# shape_setting_arduino_board.net
KiCad netlist of a schematic drawn in EAGLE
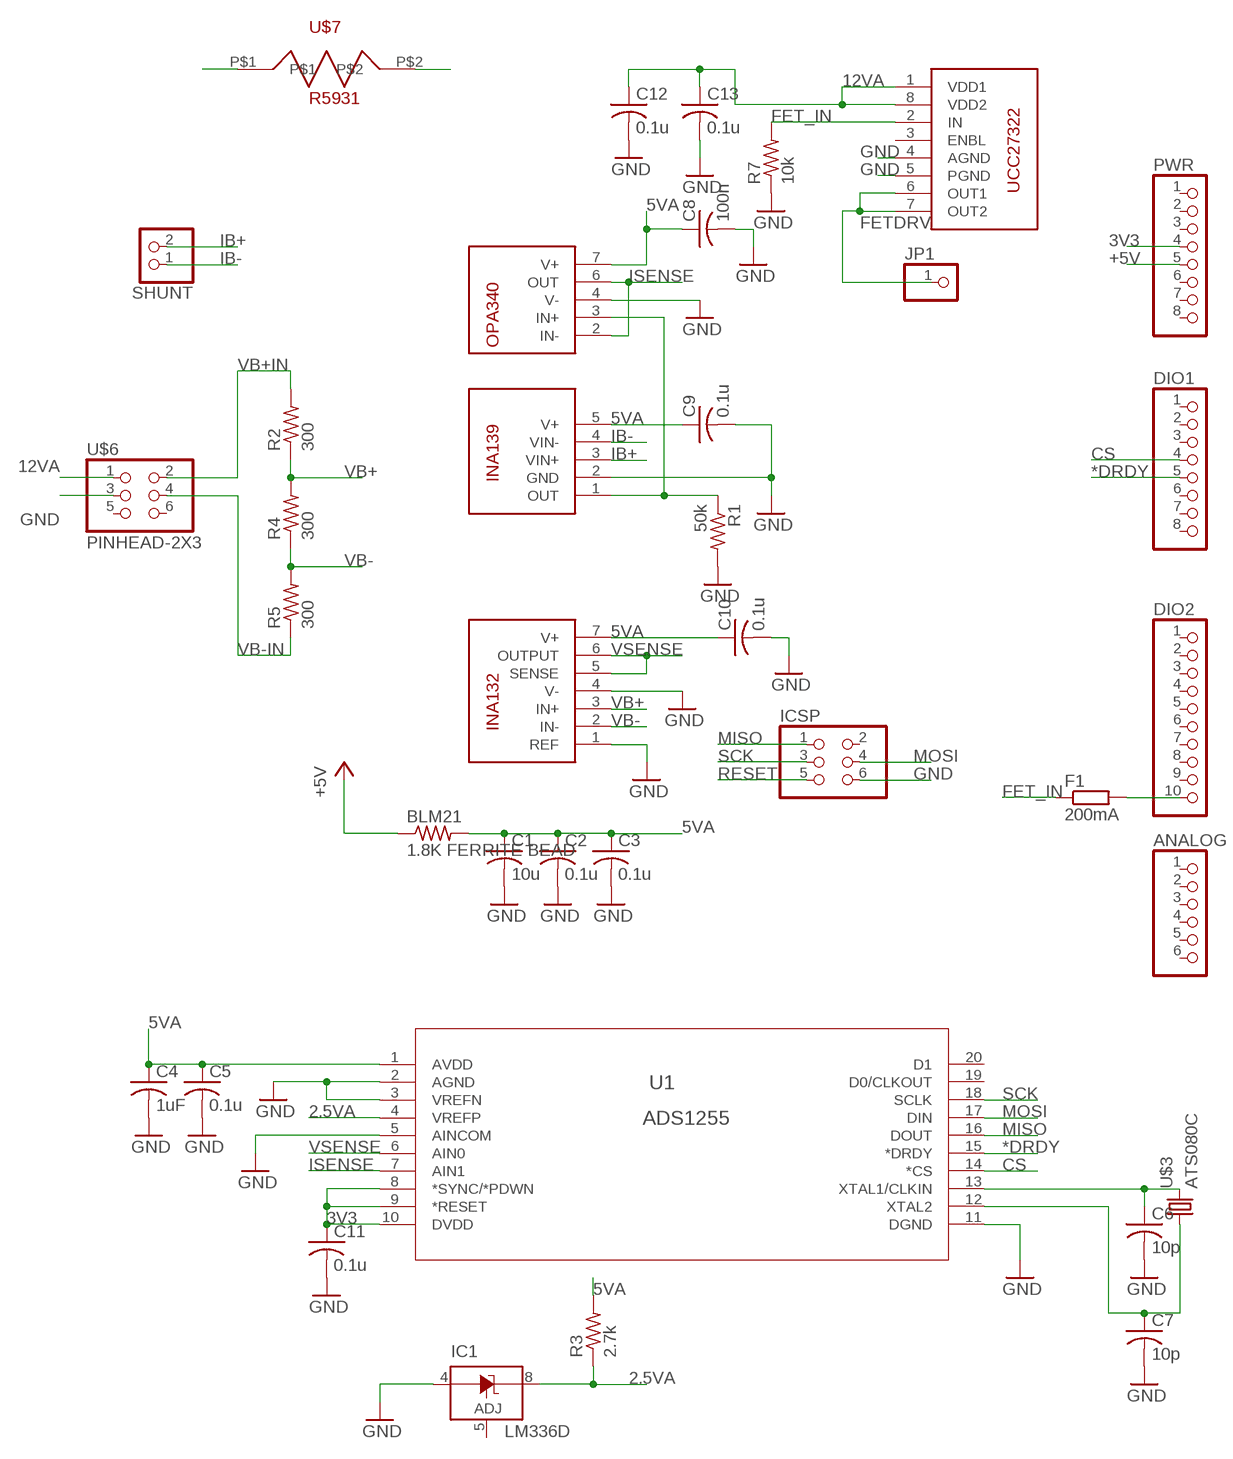
[diagram p0: schematic, sheet 1]

(export (version "E")
  (design (tool "Eeschema 10.0.6"))
  (components
    (comp (ref "ANALOG")
      (value "PINHD-1X6")
      (footprint "eagle-import:1X06")
      (libsource (lib "eagle-import") (part "PINHD-1X6"))
    )
    (comp (ref "BLM21")
      (value "1.8K FERRITE BEAD")
      (footprint "eagle-import:R0805")
      (libsource (lib "eagle-import") (part "R-US_R0805"))
    )
    (comp (ref "C1")
      (value "10u")
      (footprint "eagle-import:C0805")
      (libsource (lib "eagle-import") (part "C-USC0805"))
    )
    (comp (ref "C2")
      (value "0.1u")
      (footprint "eagle-import:C0603")
      (libsource (lib "eagle-import") (part "C-USC0603"))
    )
    (comp (ref "C3")
      (value "0.1u")
      (footprint "eagle-import:C0603")
      (libsource (lib "eagle-import") (part "C-USC0603"))
    )
    (comp (ref "C4")
      (value "1uF")
      (footprint "eagle-import:C0805")
      (libsource (lib "eagle-import") (part "C-USC0805"))
    )
    (comp (ref "C5")
      (value "0.1u")
      (footprint "eagle-import:C0603")
      (libsource (lib "eagle-import") (part "C-USC0603"))
    )
    (comp (ref "C6")
      (value "10p")
      (footprint "eagle-import:C0603")
      (libsource (lib "eagle-import") (part "C-USC0603"))
    )
    (comp (ref "C7")
      (value "10p")
      (footprint "eagle-import:C0603")
      (libsource (lib "eagle-import") (part "C-USC0603"))
    )
    (comp (ref "C8")
      (value "100n")
      (footprint "eagle-import:C0603")
      (libsource (lib "eagle-import") (part "C-USC0603"))
    )
    (comp (ref "C9")
      (value "0.1u")
      (footprint "eagle-import:C0603")
      (libsource (lib "eagle-import") (part "C-USC0603"))
    )
    (comp (ref "C10")
      (value "0.1u")
      (footprint "eagle-import:C0603")
      (libsource (lib "eagle-import") (part "C-USC0603"))
    )
    (comp (ref "C11")
      (value "0.1u")
      (footprint "eagle-import:C0603")
      (libsource (lib "eagle-import") (part "C-USC0603"))
    )
    (comp (ref "C12")
      (value "0.1u")
      (footprint "eagle-import:C0603")
      (libsource (lib "eagle-import") (part "C-USC0603"))
    )
    (comp (ref "C13")
      (value "0.1u")
      (footprint "eagle-import:C0603")
      (libsource (lib "eagle-import") (part "C-USC0603"))
    )
    (comp (ref "DIO1")
      (value "PINHD-1X8")
      (footprint "eagle-import:1X08")
      (libsource (lib "eagle-import") (part "PINHD-1X8"))
    )
    (comp (ref "DIO2")
      (value "PINHD-1X10")
      (footprint "eagle-import:1X10")
      (libsource (lib "eagle-import") (part "PINHD-1X10"))
    )
    (comp (ref "F1")
      (value "200mA")
      (footprint "eagle-import:R0603")
      (libsource (lib "eagle-import") (part "R-EU_R0603"))
    )
    (comp (ref "IC1")
      (value "LM336D")
      (footprint "eagle-import:SO08")
      (libsource (lib "eagle-import") (part "LM336D"))
    )
    (comp (ref "ICSP")
      (value "PINHD-2X3")
      (footprint "eagle-import:2X03")
      (libsource (lib "eagle-import") (part "PINHD-2X3"))
    )
    (comp (ref "JP1")
      (value "PINHD-1X1")
      (footprint "eagle-import:1X01")
      (libsource (lib "eagle-import") (part "PINHD-1X1"))
    )
    (comp (ref "PWR")
      (value "PINHD-1X8")
      (footprint "eagle-import:1X08")
      (libsource (lib "eagle-import") (part "PINHD-1X8"))
    )
    (comp (ref "R1")
      (value "50k")
      (footprint "eagle-import:R0603")
      (libsource (lib "eagle-import") (part "R-US_R0603"))
    )
    (comp (ref "R2")
      (value "300")
      (footprint "eagle-import:R0603")
      (libsource (lib "eagle-import") (part "R-US_R0603"))
    )
    (comp (ref "R3")
      (value "2.7k")
      (footprint "eagle-import:R0603")
      (libsource (lib "eagle-import") (part "R-US_R0603"))
    )
    (comp (ref "R4")
      (value "300")
      (footprint "eagle-import:R0603")
      (libsource (lib "eagle-import") (part "R-US_R0603"))
    )
    (comp (ref "R5")
      (value "300")
      (footprint "eagle-import:R0603")
      (libsource (lib "eagle-import") (part "R-US_R0603"))
    )
    (comp (ref "R7")
      (value "10k")
      (footprint "eagle-import:R0603")
      (libsource (lib "eagle-import") (part "R-US_R0603"))
    )
    (comp (ref "SHUNT")
      (value "PINHD-1X2")
      (footprint "eagle-import:1X02")
      (libsource (lib "eagle-import") (part "PINHD-1X2"))
    )
    (comp (ref "U$1")
      (value "INA139")
      (footprint "eagle-import:SOT-23(DBV)")
      (libsource (lib "eagle-import") (part "INA139"))
    )
    (comp (ref "U$2")
      (value "INA132U")
      (footprint "eagle-import:8SOIC(D)")
      (libsource (lib "eagle-import") (part "INA132U"))
    )
    (comp (ref "U$3")
      (value "ATS080C")
      (footprint "eagle-import:ATS")
      (libsource (lib "eagle-import") (part "ATS080C"))
    )
    (comp (ref "U$4")
      (value "OPA340")
      (footprint "eagle-import:8SOIC(D)")
      (libsource (lib "eagle-import") (part "OPA340"))
    )
    (comp (ref "U$5")
      (value "UCC27322")
      (footprint "eagle-import:8SOIC(D)")
      (libsource (lib "eagle-import") (part "UCC27322"))
    )
    (comp (ref "U$6")
      (value "PINHEAD-2X3")
      (footprint "eagle-import:2X03")
      (libsource (lib "eagle-import") (part "PINHEAD-2X3"))
    )
    (comp (ref "U$7")
      (value "R5931")
      (footprint "eagle-import:5931")
      (libsource (lib "eagle-import") (part "R5931"))
    )
    (comp (ref "U1")
      (value "ADS1255")
      (footprint "eagle-import:DB20")
      (fields (field (name "MANUFACTURER") "Texas Instruments"))
      (libsource (lib "eagle-import") (part "ADS1255_DB_20"))
    )
  )
  (nets
    (net (code "1") (name "+5V") (class "Default")
      (node (ref "BLM21") (pin "1") (pinfunction "1_1") (pintype "passive"))
      (node (ref "PWR") (pin "5") (pinfunction "5_5") (pintype "passive"))
    )
    (net (code "2") (name "/*DRDY") (class "Default")
      (node (ref "DIO1") (pin "5") (pinfunction "5_5") (pintype "passive"))
      (node (ref "U1") (pin "15") (pinfunction "*DRDY_15") (pintype "output"))
    )
    (net (code "3") (name "/2.5VA") (class "Default")
      (node (ref "IC1") (pin "8") (pinfunction "C_8") (pintype "passive"))
      (node (ref "R3") (pin "1") (pinfunction "1_1") (pintype "passive"))
      (node (ref "U1") (pin "4") (pinfunction "VREFP_4") (pintype "input"))
    )
    (net (code "4") (name "/3V3") (class "Default")
      (node (ref "C11") (pin "1") (pinfunction "1_1") (pintype "passive"))
      (node (ref "PWR") (pin "4") (pinfunction "4_4") (pintype "passive"))
      (node (ref "U1") (pin "10") (pinfunction "DVDD_10") (pintype "power_in"))
      (node (ref "U1") (pin "8") (pinfunction "*SYNC/*PDWN_8") (pintype "input"))
      (node (ref "U1") (pin "9") (pinfunction "*RESET_9") (pintype "input"))
    )
    (net (code "5") (name "/5VA") (class "Default")
      (node (ref "BLM21") (pin "2") (pinfunction "2_2") (pintype "passive"))
      (node (ref "C1") (pin "1") (pinfunction "1_1") (pintype "passive"))
      (node (ref "C10") (pin "1") (pinfunction "1_1") (pintype "passive"))
      (node (ref "C2") (pin "1") (pinfunction "1_1") (pintype "passive"))
      (node (ref "C3") (pin "1") (pinfunction "1_1") (pintype "passive"))
      (node (ref "C4") (pin "1") (pinfunction "1_1") (pintype "passive"))
      (node (ref "C5") (pin "1") (pinfunction "1_1") (pintype "passive"))
      (node (ref "C8") (pin "1") (pinfunction "1_1") (pintype "passive"))
      (node (ref "C9") (pin "1") (pinfunction "1_1") (pintype "passive"))
      (node (ref "R3") (pin "2") (pinfunction "2_2") (pintype "passive"))
      (node (ref "U$1") (pin "5") (pinfunction "V+_5") (pintype "bidirectional"))
      (node (ref "U$2") (pin "7") (pinfunction "V+_7") (pintype "bidirectional"))
      (node (ref "U$4") (pin "7") (pinfunction "V+_7") (pintype "bidirectional"))
      (node (ref "U1") (pin "1") (pinfunction "AVDD_1") (pintype "power_in"))
    )
    (net (code "6") (name "/12VA") (class "Default")
      (node (ref "C12") (pin "1") (pinfunction "1_1") (pintype "passive"))
      (node (ref "C13") (pin "1") (pinfunction "1_1") (pintype "passive"))
      (node (ref "U$5") (pin "1") (pinfunction "VDD1_1") (pintype "bidirectional"))
      (node (ref "U$5") (pin "8") (pinfunction "VDD2_8") (pintype "bidirectional"))
      (node (ref "U$6") (pin "1") (pinfunction "1_1") (pintype "passive"))
    )
    (net (code "7") (name "/CS") (class "Default")
      (node (ref "DIO1") (pin "4") (pinfunction "4_4") (pintype "passive"))
      (node (ref "U1") (pin "14") (pinfunction "*CS_14") (pintype "input"))
    )
    (net (code "8") (name "/FETDRV") (class "Default")
      (node (ref "JP1") (pin "1") (pinfunction "1_1") (pintype "passive"))
      (node (ref "U$5") (pin "6") (pinfunction "OUT1_6") (pintype "bidirectional"))
      (node (ref "U$5") (pin "7") (pinfunction "OUT2_7") (pintype "bidirectional"))
    )
    (net (code "9") (name "/FET_IN") (class "Default")
      (node (ref "F1") (pin "1") (pinfunction "1_1") (pintype "passive"))
      (node (ref "R7") (pin "2") (pinfunction "2_2") (pintype "passive"))
      (node (ref "U$5") (pin "2") (pinfunction "IN_2") (pintype "bidirectional"))
    )
    (net (code "10") (name "/IB+") (class "Default")
      (node (ref "SHUNT") (pin "2") (pinfunction "2_2") (pintype "passive"))
      (node (ref "U$1") (pin "3") (pinfunction "VIN+_3") (pintype "bidirectional"))
    )
    (net (code "11") (name "/IB-") (class "Default")
      (node (ref "SHUNT") (pin "1") (pinfunction "1_1") (pintype "passive"))
      (node (ref "U$1") (pin "4") (pinfunction "VIN-_4") (pintype "bidirectional"))
    )
    (net (code "12") (name "/ISENSE") (class "Default")
      (node (ref "U$4") (pin "2") (pinfunction "IN-_2") (pintype "bidirectional"))
      (node (ref "U$4") (pin "6") (pinfunction "OUT_6") (pintype "bidirectional"))
      (node (ref "U1") (pin "7") (pinfunction "AIN1_7") (pintype "input"))
    )
    (net (code "13") (name "/MISO") (class "Default")
      (node (ref "ICSP") (pin "1") (pinfunction "1_1") (pintype "passive"))
      (node (ref "U1") (pin "16") (pinfunction "DOUT_16") (pintype "output"))
    )
    (net (code "14") (name "/MOSI") (class "Default")
      (node (ref "ICSP") (pin "4") (pinfunction "4_4") (pintype "passive"))
      (node (ref "U1") (pin "17") (pinfunction "DIN_17") (pintype "input"))
    )
    (net (code "15") (name "/RESET") (class "Default")
      (node (ref "ICSP") (pin "5") (pinfunction "5_5") (pintype "passive"))
    )
    (net (code "16") (name "/SCK") (class "Default")
      (node (ref "ICSP") (pin "3") (pinfunction "3_3") (pintype "passive"))
      (node (ref "U1") (pin "18") (pinfunction "SCLK_18") (pintype "input"))
    )
    (net (code "17") (name "/VB+") (class "Default")
      (node (ref "R2") (pin "1") (pinfunction "1_1") (pintype "passive"))
      (node (ref "R4") (pin "2") (pinfunction "2_2") (pintype "passive"))
      (node (ref "U$2") (pin "3") (pinfunction "IN+_3") (pintype "bidirectional"))
    )
    (net (code "18") (name "/VB+IN") (class "Default")
      (node (ref "R2") (pin "2") (pinfunction "2_2") (pintype "passive"))
      (node (ref "U$6") (pin "2") (pinfunction "2_2") (pintype "passive"))
    )
    (net (code "19") (name "/VB-") (class "Default")
      (node (ref "R4") (pin "1") (pinfunction "1_1") (pintype "passive"))
      (node (ref "R5") (pin "2") (pinfunction "2_2") (pintype "passive"))
      (node (ref "U$2") (pin "2") (pinfunction "IN-_2") (pintype "bidirectional"))
    )
    (net (code "20") (name "/VB-IN") (class "Default")
      (node (ref "R5") (pin "1") (pinfunction "1_1") (pintype "passive"))
      (node (ref "U$6") (pin "4") (pinfunction "4_4") (pintype "passive"))
    )
    (net (code "21") (name "/VSENSE") (class "Default")
      (node (ref "U$2") (pin "5") (pinfunction "SENSE_5") (pintype "bidirectional"))
      (node (ref "U$2") (pin "6") (pinfunction "OUTPUT_6") (pintype "bidirectional"))
      (node (ref "U1") (pin "6") (pinfunction "AIN0_6") (pintype "input"))
    )
    (net (code "22") (name "GND") (class "Default")
      (node (ref "C1") (pin "2") (pinfunction "2_2") (pintype "passive"))
      (node (ref "C10") (pin "2") (pinfunction "2_2") (pintype "passive"))
      (node (ref "C11") (pin "2") (pinfunction "2_2") (pintype "passive"))
      (node (ref "C12") (pin "2") (pinfunction "2_2") (pintype "passive"))
      (node (ref "C13") (pin "2") (pinfunction "2_2") (pintype "passive"))
      (node (ref "C2") (pin "2") (pinfunction "2_2") (pintype "passive"))
      (node (ref "C3") (pin "2") (pinfunction "2_2") (pintype "passive"))
      (node (ref "C4") (pin "2") (pinfunction "2_2") (pintype "passive"))
      (node (ref "C5") (pin "2") (pinfunction "2_2") (pintype "passive"))
      (node (ref "C6") (pin "2") (pinfunction "2_2") (pintype "passive"))
      (node (ref "C7") (pin "2") (pinfunction "2_2") (pintype "passive"))
      (node (ref "C8") (pin "2") (pinfunction "2_2") (pintype "passive"))
      (node (ref "C9") (pin "2") (pinfunction "2_2") (pintype "passive"))
      (node (ref "IC1") (pin "4") (pinfunction "A_4") (pintype "input"))
      (node (ref "ICSP") (pin "6") (pinfunction "6_6") (pintype "passive"))
      (node (ref "R1") (pin "2") (pinfunction "2_2") (pintype "passive"))
      (node (ref "R7") (pin "1") (pinfunction "1_1") (pintype "passive"))
      (node (ref "U$1") (pin "2") (pinfunction "GND_2") (pintype "bidirectional"))
      (node (ref "U$2") (pin "1") (pinfunction "REF_1") (pintype "bidirectional"))
      (node (ref "U$2") (pin "4") (pinfunction "V-_4") (pintype "bidirectional"))
      (node (ref "U$4") (pin "4") (pinfunction "V-_4") (pintype "bidirectional"))
      (node (ref "U$5") (pin "4") (pinfunction "AGND_4") (pintype "bidirectional"))
      (node (ref "U$5") (pin "5") (pinfunction "PGND_5") (pintype "bidirectional"))
      (node (ref "U$6") (pin "3") (pinfunction "3_3") (pintype "passive"))
      (node (ref "U1") (pin "11") (pinfunction "DGND_11") (pintype "power_in"))
      (node (ref "U1") (pin "2") (pinfunction "AGND_2") (pintype "power_in"))
      (node (ref "U1") (pin "3") (pinfunction "VREFN_3") (pintype "input"))
      (node (ref "U1") (pin "5") (pinfunction "AINCOM_5") (pintype "input"))
    )
    (net (code "23") (name "Net-(DIO2-Pad10)") (class "Default")
      (node (ref "DIO2") (pin "10") (pinfunction "10_10") (pintype "passive"))
      (node (ref "F1") (pin "2") (pinfunction "2_2") (pintype "passive"))
    )
    (net (code "24") (name "Net-(U$1-OUT)") (class "Default")
      (node (ref "R1") (pin "1") (pinfunction "1_1") (pintype "passive"))
      (node (ref "U$1") (pin "1") (pinfunction "OUT_1") (pintype "bidirectional"))
      (node (ref "U$4") (pin "3") (pinfunction "IN+_3") (pintype "bidirectional"))
    )
    (net (code "25") (name "Net-(U1-XTAL1{slash}CLKIN)") (class "Default")
      (node (ref "C6") (pin "1") (pinfunction "1_1") (pintype "passive"))
      (node (ref "U$3") (pin "2") (pinfunction "2_2") (pintype "passive"))
      (node (ref "U1") (pin "13") (pinfunction "XTAL1/CLKIN_13") (pintype "passive"))
    )
    (net (code "26") (name "Net-(U1-XTAL2)") (class "Default")
      (node (ref "C7") (pin "1") (pinfunction "1_1") (pintype "passive"))
      (node (ref "U$3") (pin "1") (pinfunction "1_1") (pintype "passive"))
      (node (ref "U1") (pin "12") (pinfunction "XTAL2_12") (pintype "passive"))
    )
    (net (code "27") (name "unconnected-(ANALOG-Pad1)") (class "Default")
      (node (ref "ANALOG") (pin "1") (pinfunction "1_1") (pintype "passive"))
    )
    (net (code "28") (name "unconnected-(ANALOG-Pad2)") (class "Default")
      (node (ref "ANALOG") (pin "2") (pinfunction "2_2") (pintype "passive"))
    )
    (net (code "29") (name "unconnected-(ANALOG-Pad3)") (class "Default")
      (node (ref "ANALOG") (pin "3") (pinfunction "3_3") (pintype "passive"))
    )
    (net (code "30") (name "unconnected-(ANALOG-Pad4)") (class "Default")
      (node (ref "ANALOG") (pin "4") (pinfunction "4_4") (pintype "passive"))
    )
    (net (code "31") (name "unconnected-(ANALOG-Pad5)") (class "Default")
      (node (ref "ANALOG") (pin "5") (pinfunction "5_5") (pintype "passive"))
    )
    (net (code "32") (name "unconnected-(ANALOG-Pad6)") (class "Default")
      (node (ref "ANALOG") (pin "6") (pinfunction "6_6") (pintype "passive"))
    )
    (net (code "33") (name "unconnected-(DIO1-Pad1)") (class "Default")
      (node (ref "DIO1") (pin "1") (pinfunction "1_1") (pintype "passive"))
    )
    (net (code "34") (name "unconnected-(DIO1-Pad2)") (class "Default")
      (node (ref "DIO1") (pin "2") (pinfunction "2_2") (pintype "passive"))
    )
    (net (code "35") (name "unconnected-(DIO1-Pad3)") (class "Default")
      (node (ref "DIO1") (pin "3") (pinfunction "3_3") (pintype "passive"))
    )
    (net (code "36") (name "unconnected-(DIO1-Pad6)") (class "Default")
      (node (ref "DIO1") (pin "6") (pinfunction "6_6") (pintype "passive"))
    )
    (net (code "37") (name "unconnected-(DIO1-Pad7)") (class "Default")
      (node (ref "DIO1") (pin "7") (pinfunction "7_7") (pintype "passive"))
    )
    (net (code "38") (name "unconnected-(DIO1-Pad8)") (class "Default")
      (node (ref "DIO1") (pin "8") (pinfunction "8_8") (pintype "passive"))
    )
    (net (code "39") (name "unconnected-(DIO2-Pad1)") (class "Default")
      (node (ref "DIO2") (pin "1") (pinfunction "1_1") (pintype "passive"))
    )
    (net (code "40") (name "unconnected-(DIO2-Pad2)") (class "Default")
      (node (ref "DIO2") (pin "2") (pinfunction "2_2") (pintype "passive"))
    )
    (net (code "41") (name "unconnected-(DIO2-Pad3)") (class "Default")
      (node (ref "DIO2") (pin "3") (pinfunction "3_3") (pintype "passive"))
    )
    (net (code "42") (name "unconnected-(DIO2-Pad4)") (class "Default")
      (node (ref "DIO2") (pin "4") (pinfunction "4_4") (pintype "passive"))
    )
    (net (code "43") (name "unconnected-(DIO2-Pad5)") (class "Default")
      (node (ref "DIO2") (pin "5") (pinfunction "5_5") (pintype "passive"))
    )
    (net (code "44") (name "unconnected-(DIO2-Pad6)") (class "Default")
      (node (ref "DIO2") (pin "6") (pinfunction "6_6") (pintype "passive"))
    )
    (net (code "45") (name "unconnected-(DIO2-Pad7)") (class "Default")
      (node (ref "DIO2") (pin "7") (pinfunction "7_7") (pintype "passive"))
    )
    (net (code "46") (name "unconnected-(DIO2-Pad8)") (class "Default")
      (node (ref "DIO2") (pin "8") (pinfunction "8_8") (pintype "passive"))
    )
    (net (code "47") (name "unconnected-(DIO2-Pad9)") (class "Default")
      (node (ref "DIO2") (pin "9") (pinfunction "9_9") (pintype "passive"))
    )
    (net (code "48") (name "unconnected-(IC1-ADJ-Pad5)") (class "Default")
      (node (ref "IC1") (pin "5") (pinfunction "ADJ_5") (pintype "input"))
    )
    (net (code "49") (name "unconnected-(ICSP-Pad2)") (class "Default")
      (node (ref "ICSP") (pin "2") (pinfunction "2_2") (pintype "passive"))
    )
    (net (code "50") (name "unconnected-(PWR-Pad1)") (class "Default")
      (node (ref "PWR") (pin "1") (pinfunction "1_1") (pintype "passive"))
    )
    (net (code "51") (name "unconnected-(PWR-Pad2)") (class "Default")
      (node (ref "PWR") (pin "2") (pinfunction "2_2") (pintype "passive"))
    )
    (net (code "52") (name "unconnected-(PWR-Pad3)") (class "Default")
      (node (ref "PWR") (pin "3") (pinfunction "3_3") (pintype "passive"))
    )
    (net (code "53") (name "unconnected-(PWR-Pad6)") (class "Default")
      (node (ref "PWR") (pin "6") (pinfunction "6_6") (pintype "passive"))
    )
    (net (code "54") (name "unconnected-(PWR-Pad7)") (class "Default")
      (node (ref "PWR") (pin "7") (pinfunction "7_7") (pintype "passive"))
    )
    (net (code "55") (name "unconnected-(PWR-Pad8)") (class "Default")
      (node (ref "PWR") (pin "8") (pinfunction "8_8") (pintype "passive"))
    )
    (net (code "56") (name "unconnected-(U$5-ENBL-Pad3)") (class "Default")
      (node (ref "U$5") (pin "3") (pinfunction "ENBL_3") (pintype "bidirectional"))
    )
    (net (code "57") (name "unconnected-(U$6-Pad5)") (class "Default")
      (node (ref "U$6") (pin "5") (pinfunction "5_5") (pintype "passive"))
    )
    (net (code "58") (name "unconnected-(U$6-Pad6)") (class "Default")
      (node (ref "U$6") (pin "6") (pinfunction "6_6") (pintype "passive"))
    )
    (net (code "59") (name "unconnected-(U$7-PadP$1)") (class "Default")
      (node (ref "U$7") (pin "P$1") (pinfunction "P$1_P$1") (pintype "bidirectional"))
    )
    (net (code "60") (name "unconnected-(U$7-PadP$2)") (class "Default")
      (node (ref "U$7") (pin "P$2") (pinfunction "P$2_P$2") (pintype "bidirectional"))
    )
    (net (code "61") (name "unconnected-(U1-D0{slash}CLKOUT-Pad19)") (class "Default")
      (node (ref "U1") (pin "19") (pinfunction "D0/CLKOUT_19") (pintype "bidirectional"))
    )
    (net (code "62") (name "unconnected-(U1-D1-Pad20)") (class "Default")
      (node (ref "U1") (pin "20") (pinfunction "D1_20") (pintype "bidirectional"))
    )
  )
)
